# ALU_Desgn.net
KiCad netlist of a schematic drawn in Altium Designer
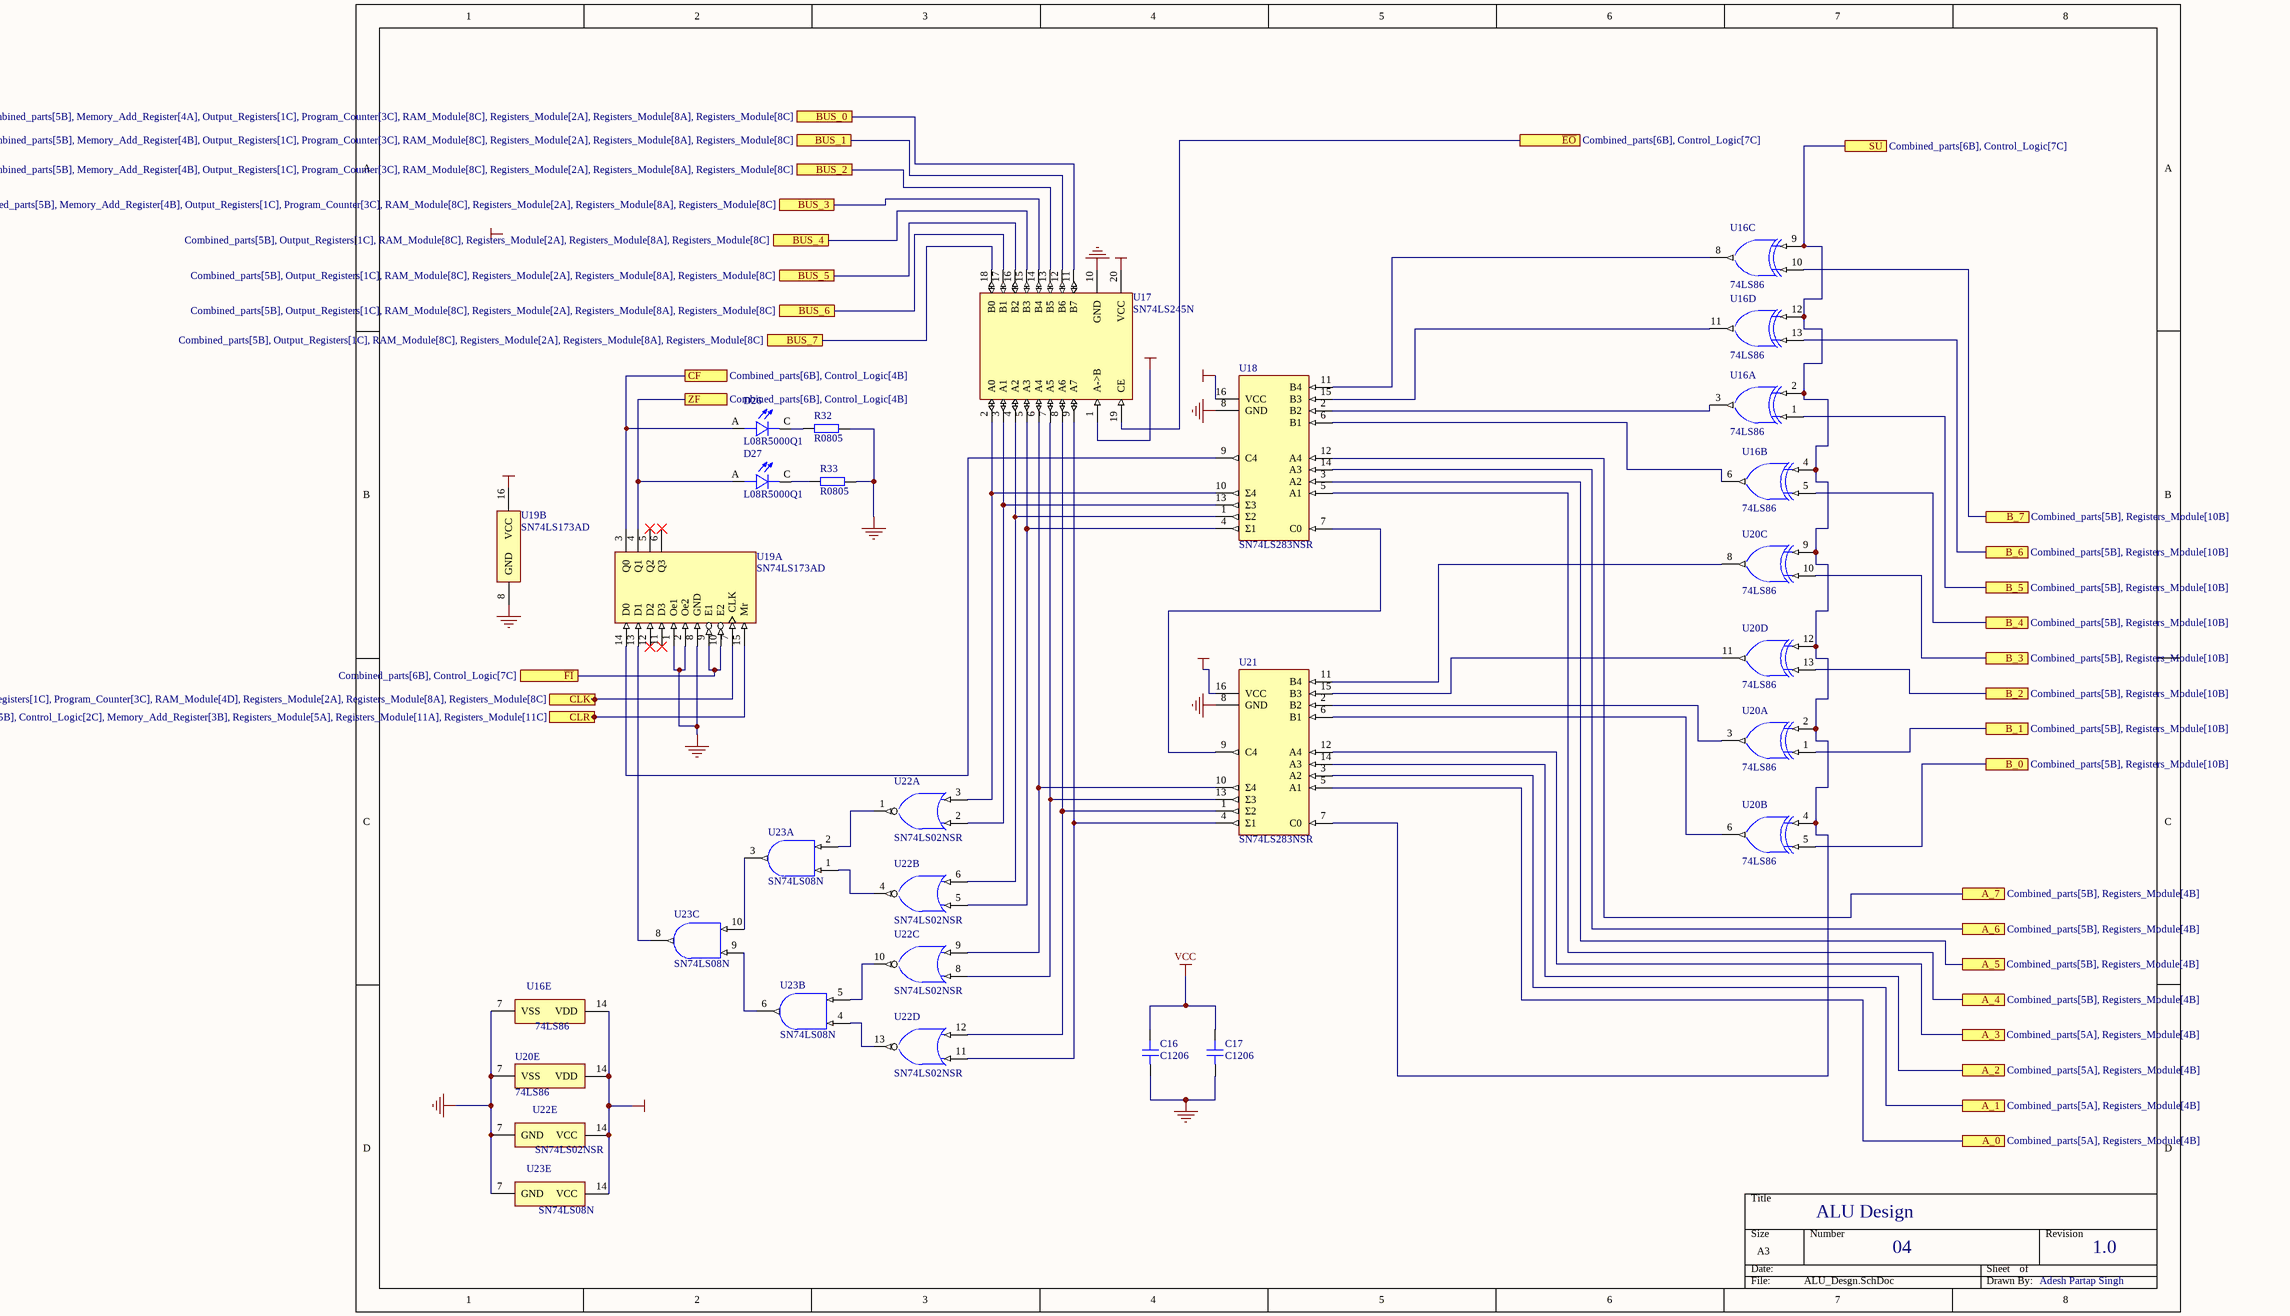
[diagram p0: ALU_Desgn.SchDoc]

(export (version "E")
  (design (tool "Eeschema 10.0.6"))
  (components
    (comp (ref "C16")
      (value "C1206")
      (footprint "CAP_1206")
      (description "Capacitor SMD 1206")
      (libsource (lib "Schematic-Lib-PhilsLab") (part "CAP_1206"))
    )
    (comp (ref "C17")
      (value "C1206")
      (footprint "CAP_1206")
      (description "Capacitor SMD 1206")
      (libsource (lib "Schematic-Lib-PhilsLab") (part "CAP_1206"))
    )
    (comp (ref "D26")
      (value "L08R5000Q1")
      (footprint "LEDRD254W57D500H1070")
      (fields (field (name "MF") "LED Technology"))
      (libsource (lib "8BIT_COMP_LIB") (part "L08R5000Q1"))
    )
    (comp (ref "D27")
      (value "L08R5000Q1")
      (footprint "LEDRD254W57D500H1070")
      (fields (field (name "MF") "LED Technology"))
      (libsource (lib "8BIT_COMP_LIB") (part "L08R5000Q1"))
    )
    (comp (ref "R32")
      (value "R0805")
      (footprint "RES_0805")
      (description "Resistor SMD 0805")
      (libsource (lib "Schematic-Lib-PhilsLab") (part "RES_0805"))
    )
    (comp (ref "R33")
      (value "R0805")
      (footprint "RES_0805")
      (description "Resistor SMD 0805")
      (libsource (lib "Schematic-Lib-PhilsLab") (part "RES_0805"))
    )
    (comp (ref "U16")
      (value "74LS86")
      (footprint "D14")
      (description "XOR (Exclusive OR) IC 4 Channel 14-PDIP")
      (fields
        (field (name "MANUFACTURER") "Texas Instruments")
        (field (name "GENERIC PART NUMBER") "CD4030B")
      )
      (libsource (lib "8BIT_COMP_LIB") (part "74LS86"))
    )
    (comp (ref "U17")
      (value "SN74LS245N")
      (footprint "FP-N0020A-MFG")
      (description "IC TXRX NON-INVERT 5.25V 20DIP")
      (libsource (lib "8BIT_COMP_LIB") (part "CMP-1620-00419-3"))
    )
    (comp (ref "U18")
      (value "SN74LS283NSR")
      (footprint "NS0016A_L")
      (description "4-Bit Binary Full Adders With Fast Carry, NS0016A, LARGE T&R")
      (fields
        (field (name "GENERIC PART NUMBER") "SN74LS283")
        (field (name "MANUFACTURER") "Texas Instruments")
      )
      (libsource (lib "8BIT_COMP_LIB") (part "CMP-1623-00603-2"))
    )
    (comp (ref "U19")
      (value "SN74LS173AD")
      (footprint "D0016A_N")
      (description "4-Bit D-type Registers with 3-State Outputs, D0016A, TUBE")
      (fields
        (field (name "GENERIC PART NUMBER") "SN74LS173A")
        (field (name "MANUFACTURER") "Texas Instruments")
      )
      (libsource (lib "8BIT_COMP_LIB") (part "CMP-1616-00008-3"))
    )
    (comp (ref "U20")
      (value "74LS86")
      (footprint "D14")
      (description "XOR (Exclusive OR) IC 4 Channel 14-PDIP")
      (fields
        (field (name "MANUFACTURER") "Texas Instruments")
        (field (name "GENERIC PART NUMBER") "CD4030B")
      )
      (libsource (lib "8BIT_COMP_LIB") (part "74LS86"))
    )
    (comp (ref "U21")
      (value "SN74LS283NSR")
      (footprint "NS0016A_L")
      (description "4-Bit Binary Full Adders With Fast Carry, NS0016A, LARGE T&R")
      (fields
        (field (name "GENERIC PART NUMBER") "SN74LS283")
        (field (name "MANUFACTURER") "Texas Instruments")
      )
      (libsource (lib "8BIT_COMP_LIB") (part "CMP-1623-00603-2"))
    )
    (comp (ref "U22")
      (value "SN74LS02NSR")
      (footprint "NS0014A_M")
      (description "Quad 2-input positive-NOR gates, NS0014A, LARGE T&R")
      (fields
        (field (name "MANUFACTURER") "Texas Instruments")
        (field (name "GENERIC PART NUMBER") "SN74LS02")
      )
      (libsource (lib "Altium Content Vault") (part "CMP-0806-00215-4"))
    )
    (comp (ref "U23")
      (value "SN74LS08N")
      (footprint "N0014A")
      (description "Quadruple 2-Input Positive-AND Gates, N0014A, TUBE")
      (fields
        (field (name "MANUFACTURER") "Texas Instruments")
        (field (name "GENERIC PART NUMBER") "SN74LS08")
      )
      (libsource (lib "8BIT_COMP_LIB") (part "CMP-0777-00259-3"))
    )
  )
  (nets
    (net (code "1") (name "/A_0") (class "Default")
      (node (ref "U21") (pin "5") (pinfunction "A1_5") (pintype "input"))
    )
    (net (code "2") (name "/A_1") (class "Default")
      (node (ref "U21") (pin "3") (pinfunction "A2_3") (pintype "input"))
    )
    (net (code "3") (name "/A_2") (class "Default")
      (node (ref "U21") (pin "14") (pinfunction "A3_14") (pintype "input"))
    )
    (net (code "4") (name "/A_3") (class "Default")
      (node (ref "U21") (pin "12") (pinfunction "A4_12") (pintype "input"))
    )
    (net (code "5") (name "/A_4") (class "Default")
      (node (ref "U18") (pin "5") (pinfunction "A1_5") (pintype "input"))
    )
    (net (code "6") (name "/A_5") (class "Default")
      (node (ref "U18") (pin "3") (pinfunction "A2_3") (pintype "input"))
    )
    (net (code "7") (name "/A_6") (class "Default")
      (node (ref "U18") (pin "14") (pinfunction "A3_14") (pintype "input"))
    )
    (net (code "8") (name "/A_7") (class "Default")
      (node (ref "U18") (pin "12") (pinfunction "A4_12") (pintype "input"))
    )
    (net (code "9") (name "/BUS_0") (class "Default")
      (node (ref "U17") (pin "11") (pinfunction "B7_11") (pintype "bidirectional"))
    )
    (net (code "10") (name "/BUS_1") (class "Default")
      (node (ref "U17") (pin "12") (pinfunction "B6_12") (pintype "bidirectional"))
    )
    (net (code "11") (name "/BUS_2") (class "Default")
      (node (ref "U17") (pin "13") (pinfunction "B5_13") (pintype "bidirectional"))
    )
    (net (code "12") (name "/BUS_3") (class "Default")
      (node (ref "U17") (pin "14") (pinfunction "B4_14") (pintype "bidirectional"))
    )
    (net (code "13") (name "/BUS_4") (class "Default")
      (node (ref "U17") (pin "15") (pinfunction "B3_15") (pintype "bidirectional"))
    )
    (net (code "14") (name "/BUS_5") (class "Default")
      (node (ref "U17") (pin "16") (pinfunction "B2_16") (pintype "bidirectional"))
    )
    (net (code "15") (name "/BUS_6") (class "Default")
      (node (ref "U17") (pin "17") (pinfunction "B1_17") (pintype "bidirectional"))
    )
    (net (code "16") (name "/BUS_7") (class "Default")
      (node (ref "U17") (pin "18") (pinfunction "B0_18") (pintype "bidirectional"))
    )
    (net (code "17") (name "/B_0") (class "Default")
      (node (ref "U20") (pin "5") (pinfunction "C_5") (pintype "input"))
    )
    (net (code "18") (name "/B_1") (class "Default")
      (node (ref "U20") (pin "1") (pinfunction "A_1") (pintype "input"))
    )
    (net (code "19") (name "/B_2") (class "Default")
      (node (ref "U20") (pin "13") (pinfunction "G_13") (pintype "input"))
    )
    (net (code "20") (name "/B_3") (class "Default")
      (node (ref "U20") (pin "10") (pinfunction "E_10") (pintype "input"))
    )
    (net (code "21") (name "/B_4") (class "Default")
      (node (ref "U16") (pin "5") (pinfunction "C_5") (pintype "input"))
    )
    (net (code "22") (name "/B_5") (class "Default")
      (node (ref "U16") (pin "1") (pinfunction "A_1") (pintype "input"))
    )
    (net (code "23") (name "/B_6") (class "Default")
      (node (ref "U16") (pin "13") (pinfunction "G_13") (pintype "input"))
    )
    (net (code "24") (name "/B_7") (class "Default")
      (node (ref "U16") (pin "10") (pinfunction "E_10") (pintype "input"))
    )
    (net (code "25") (name "/CF") (class "Default")
      (node (ref "D26") (pin "A") (pinfunction "A_A") (pintype "passive"))
      (node (ref "U19") (pin "3") (pinfunction "Q0_3") (pintype "tri_state"))
    )
    (net (code "26") (name "/CLK") (class "Default")
      (node (ref "U19") (pin "7") (pinfunction "CLK_7") (pintype "input"))
    )
    (net (code "27") (name "/CLR") (class "Default")
      (node (ref "U19") (pin "15") (pinfunction "Mr_15") (pintype "input"))
    )
    (net (code "28") (name "/SU") (class "Default")
      (node (ref "U16") (pin "12") (pinfunction "H_12") (pintype "input"))
      (node (ref "U16") (pin "2") (pinfunction "B_2") (pintype "input"))
      (node (ref "U16") (pin "4") (pinfunction "D_4") (pintype "input"))
      (node (ref "U16") (pin "9") (pinfunction "F_9") (pintype "input"))
      (node (ref "U20") (pin "12") (pinfunction "H_12") (pintype "input"))
      (node (ref "U20") (pin "2") (pinfunction "B_2") (pintype "input"))
      (node (ref "U20") (pin "4") (pinfunction "D_4") (pintype "input"))
      (node (ref "U20") (pin "9") (pinfunction "F_9") (pintype "input"))
      (node (ref "U21") (pin "7") (pinfunction "C0_7") (pintype "input"))
    )
    (net (code "29") (name "/ZF") (class "Default")
      (node (ref "D27") (pin "A") (pinfunction "A_A") (pintype "passive"))
      (node (ref "U19") (pin "4") (pinfunction "Q1_4") (pintype "tri_state"))
    )
    (net (code "30") (name "/~{EO}") (class "Default")
      (node (ref "U17") (pin "19") (pinfunction "CE_19") (pintype "input"))
    )
    (net (code "31") (name "/~{FI}") (class "Default")
      (node (ref "U19") (pin "10") (pinfunction "E2_10") (pintype "input"))
      (node (ref "U19") (pin "9") (pinfunction "E1_9") (pintype "input"))
    )
    (net (code "32") (name "GND") (class "Default")
      (node (ref "C16") (pin "1") (pinfunction "1_1") (pintype "passive"))
      (node (ref "C17") (pin "1") (pinfunction "1_1") (pintype "passive"))
      (node (ref "R32") (pin "2") (pinfunction "2_2") (pintype "passive"))
      (node (ref "R33") (pin "2") (pinfunction "2_2") (pintype "passive"))
      (node (ref "U16") (pin "7") (pinfunction "VSS_7") (pintype "power_in"))
      (node (ref "U17") (pin "10") (pinfunction "GND_10") (pintype "power_in"))
      (node (ref "U18") (pin "8") (pinfunction "GND_8") (pintype "power_in"))
      (node (ref "U19") (pin "1") (pinfunction "Oe1_1") (pintype "input"))
      (node (ref "U19") (pin "2") (pinfunction "Oe2_2") (pintype "input"))
      (node (ref "U19") (pin "8") (pinfunction "GND_8") (pintype "power_in"))
      (node (ref "U20") (pin "7") (pinfunction "VSS_7") (pintype "power_in"))
      (node (ref "U21") (pin "8") (pinfunction "GND_8") (pintype "power_in"))
      (node (ref "U22") (pin "7") (pinfunction "GND_7") (pintype "power_in"))
      (node (ref "U23") (pin "7") (pinfunction "GND_7") (pintype "power_in"))
    )
    (net (code "33") (name "Net-(D26-PadC)") (class "Default")
      (node (ref "D26") (pin "C") (pinfunction "C_C") (pintype "passive"))
      (node (ref "R32") (pin "1") (pinfunction "1_1") (pintype "passive"))
    )
    (net (code "34") (name "Net-(D27-PadC)") (class "Default")
      (node (ref "D27") (pin "C") (pinfunction "C_C") (pintype "passive"))
      (node (ref "R33") (pin "1") (pinfunction "1_1") (pintype "passive"))
    )
    (net (code "35") (name "Net-(U16A-J)") (class "Default")
      (node (ref "U16") (pin "3") (pinfunction "J_3") (pintype "output"))
      (node (ref "U18") (pin "2") (pinfunction "B2_2") (pintype "input"))
    )
    (net (code "36") (name "Net-(U16B-K)") (class "Default")
      (node (ref "U16") (pin "6") (pinfunction "K_6") (pintype "output"))
      (node (ref "U18") (pin "6") (pinfunction "B1_6") (pintype "input"))
    )
    (net (code "37") (name "Net-(U16C-L)") (class "Default")
      (node (ref "U16") (pin "8") (pinfunction "L_8") (pintype "output"))
      (node (ref "U18") (pin "11") (pinfunction "B4_11") (pintype "input"))
    )
    (net (code "38") (name "Net-(U16D-M)") (class "Default")
      (node (ref "U16") (pin "11") (pinfunction "M_11") (pintype "output"))
      (node (ref "U18") (pin "15") (pinfunction "B3_15") (pintype "input"))
    )
    (net (code "39") (name "Net-(U17-A0)") (class "Default")
      (node (ref "U17") (pin "2") (pinfunction "A0_2") (pintype "bidirectional"))
      (node (ref "U18") (pin "10") (pinfunction "Σ4_10") (pintype "output"))
      (node (ref "U22") (pin "3") (pinfunction "1B_3") (pintype "input"))
    )
    (net (code "40") (name "Net-(U17-A1)") (class "Default")
      (node (ref "U17") (pin "3") (pinfunction "A1_3") (pintype "bidirectional"))
      (node (ref "U18") (pin "13") (pinfunction "Σ3_13") (pintype "output"))
      (node (ref "U22") (pin "2") (pinfunction "1A_2") (pintype "input"))
    )
    (net (code "41") (name "Net-(U17-A2)") (class "Default")
      (node (ref "U17") (pin "4") (pinfunction "A2_4") (pintype "bidirectional"))
      (node (ref "U18") (pin "1") (pinfunction "Σ2_1") (pintype "output"))
      (node (ref "U22") (pin "6") (pinfunction "2B_6") (pintype "input"))
    )
    (net (code "42") (name "Net-(U17-A3)") (class "Default")
      (node (ref "U17") (pin "5") (pinfunction "A3_5") (pintype "bidirectional"))
      (node (ref "U18") (pin "4") (pinfunction "Σ1_4") (pintype "output"))
      (node (ref "U22") (pin "5") (pinfunction "2A_5") (pintype "input"))
    )
    (net (code "43") (name "Net-(U17-A4)") (class "Default")
      (node (ref "U17") (pin "6") (pinfunction "A4_6") (pintype "bidirectional"))
      (node (ref "U21") (pin "10") (pinfunction "Σ4_10") (pintype "output"))
      (node (ref "U22") (pin "9") (pinfunction "3B_9") (pintype "input"))
    )
    (net (code "44") (name "Net-(U17-A5)") (class "Default")
      (node (ref "U17") (pin "7") (pinfunction "A5_7") (pintype "bidirectional"))
      (node (ref "U21") (pin "13") (pinfunction "Σ3_13") (pintype "output"))
      (node (ref "U22") (pin "8") (pinfunction "3A_8") (pintype "input"))
    )
    (net (code "45") (name "Net-(U17-A6)") (class "Default")
      (node (ref "U17") (pin "8") (pinfunction "A6_8") (pintype "bidirectional"))
      (node (ref "U21") (pin "1") (pinfunction "Σ2_1") (pintype "output"))
      (node (ref "U22") (pin "12") (pinfunction "4B_12") (pintype "input"))
    )
    (net (code "46") (name "Net-(U17-A7)") (class "Default")
      (node (ref "U17") (pin "9") (pinfunction "A7_9") (pintype "bidirectional"))
      (node (ref "U21") (pin "4") (pinfunction "Σ1_4") (pintype "output"))
      (node (ref "U22") (pin "11") (pinfunction "4A_11") (pintype "input"))
    )
    (net (code "47") (name "Net-(U18-C0)") (class "Default")
      (node (ref "U18") (pin "7") (pinfunction "C0_7") (pintype "input"))
      (node (ref "U21") (pin "9") (pinfunction "C4_9") (pintype "output"))
    )
    (net (code "48") (name "Net-(U18-C4)") (class "Default")
      (node (ref "U18") (pin "9") (pinfunction "C4_9") (pintype "output"))
      (node (ref "U19") (pin "14") (pinfunction "D0_14") (pintype "input"))
    )
    (net (code "49") (name "Net-(U19A-D1)") (class "Default")
      (node (ref "U19") (pin "13") (pinfunction "D1_13") (pintype "input"))
      (node (ref "U23") (pin "8") (pinfunction "3Y_8") (pintype "output"))
    )
    (net (code "50") (name "Net-(U20A-J)") (class "Default")
      (node (ref "U20") (pin "3") (pinfunction "J_3") (pintype "output"))
      (node (ref "U21") (pin "2") (pinfunction "B2_2") (pintype "input"))
    )
    (net (code "51") (name "Net-(U20B-K)") (class "Default")
      (node (ref "U20") (pin "6") (pinfunction "K_6") (pintype "output"))
      (node (ref "U21") (pin "6") (pinfunction "B1_6") (pintype "input"))
    )
    (net (code "52") (name "Net-(U20C-L)") (class "Default")
      (node (ref "U20") (pin "8") (pinfunction "L_8") (pintype "output"))
      (node (ref "U21") (pin "11") (pinfunction "B4_11") (pintype "input"))
    )
    (net (code "53") (name "Net-(U20D-M)") (class "Default")
      (node (ref "U20") (pin "11") (pinfunction "M_11") (pintype "output"))
      (node (ref "U21") (pin "15") (pinfunction "B3_15") (pintype "input"))
    )
    (net (code "54") (name "Net-(U22A-1Y)") (class "Default")
      (node (ref "U22") (pin "1") (pinfunction "1Y_1") (pintype "output"))
      (node (ref "U23") (pin "2") (pinfunction "1B_2") (pintype "input"))
    )
    (net (code "55") (name "Net-(U22B-2Y)") (class "Default")
      (node (ref "U22") (pin "4") (pinfunction "2Y_4") (pintype "output"))
      (node (ref "U23") (pin "1") (pinfunction "1A_1") (pintype "input"))
    )
    (net (code "56") (name "Net-(U22C-3Y)") (class "Default")
      (node (ref "U22") (pin "10") (pinfunction "3Y_10") (pintype "output"))
      (node (ref "U23") (pin "5") (pinfunction "2B_5") (pintype "input"))
    )
    (net (code "57") (name "Net-(U22D-4Y)") (class "Default")
      (node (ref "U22") (pin "13") (pinfunction "4Y_13") (pintype "output"))
      (node (ref "U23") (pin "4") (pinfunction "2A_4") (pintype "input"))
    )
    (net (code "58") (name "Net-(U23A-1Y)") (class "Default")
      (node (ref "U23") (pin "10") (pinfunction "3B_10") (pintype "input"))
      (node (ref "U23") (pin "3") (pinfunction "1Y_3") (pintype "output"))
    )
    (net (code "59") (name "Net-(U23B-2Y)") (class "Default")
      (node (ref "U23") (pin "6") (pinfunction "2Y_6") (pintype "output"))
      (node (ref "U23") (pin "9") (pinfunction "3A_9") (pintype "input"))
    )
    (net (code "60") (name "VCC") (class "Default")
      (node (ref "C16") (pin "2") (pinfunction "2_2") (pintype "passive"))
      (node (ref "C17") (pin "2") (pinfunction "2_2") (pintype "passive"))
      (node (ref "U16") (pin "14") (pinfunction "VDD_14") (pintype "power_in"))
      (node (ref "U17") (pin "1") (pinfunction "A->B_1") (pintype "input"))
      (node (ref "U17") (pin "20") (pinfunction "VCC_20") (pintype "power_in"))
      (node (ref "U18") (pin "16") (pinfunction "VCC_16") (pintype "power_in"))
      (node (ref "U19") (pin "16") (pinfunction "VCC_16") (pintype "power_in"))
      (node (ref "U20") (pin "14") (pinfunction "VDD_14") (pintype "power_in"))
      (node (ref "U21") (pin "16") (pinfunction "VCC_16") (pintype "power_in"))
      (node (ref "U22") (pin "14") (pinfunction "VCC_14") (pintype "power_in"))
      (node (ref "U23") (pin "14") (pinfunction "VCC_14") (pintype "power_in"))
    )
    (net (code "61") (name "unconnected-(U19A-D2-Pad12)") (class "Default")
      (node (ref "U19") (pin "12") (pinfunction "D2_12") (pintype "input+no_connect"))
    )
    (net (code "62") (name "unconnected-(U19A-D3-Pad11)") (class "Default")
      (node (ref "U19") (pin "11") (pinfunction "D3_11") (pintype "input+no_connect"))
    )
    (net (code "63") (name "unconnected-(U19A-Q2-Pad5)") (class "Default")
      (node (ref "U19") (pin "5") (pinfunction "Q2_5") (pintype "tri_state+no_connect"))
    )
    (net (code "64") (name "unconnected-(U19A-Q3-Pad6)") (class "Default")
      (node (ref "U19") (pin "6") (pinfunction "Q3_6") (pintype "tri_state+no_connect"))
    )
  )
)
